# PL.net
KiCad netlist of a schematic drawn in EAGLE
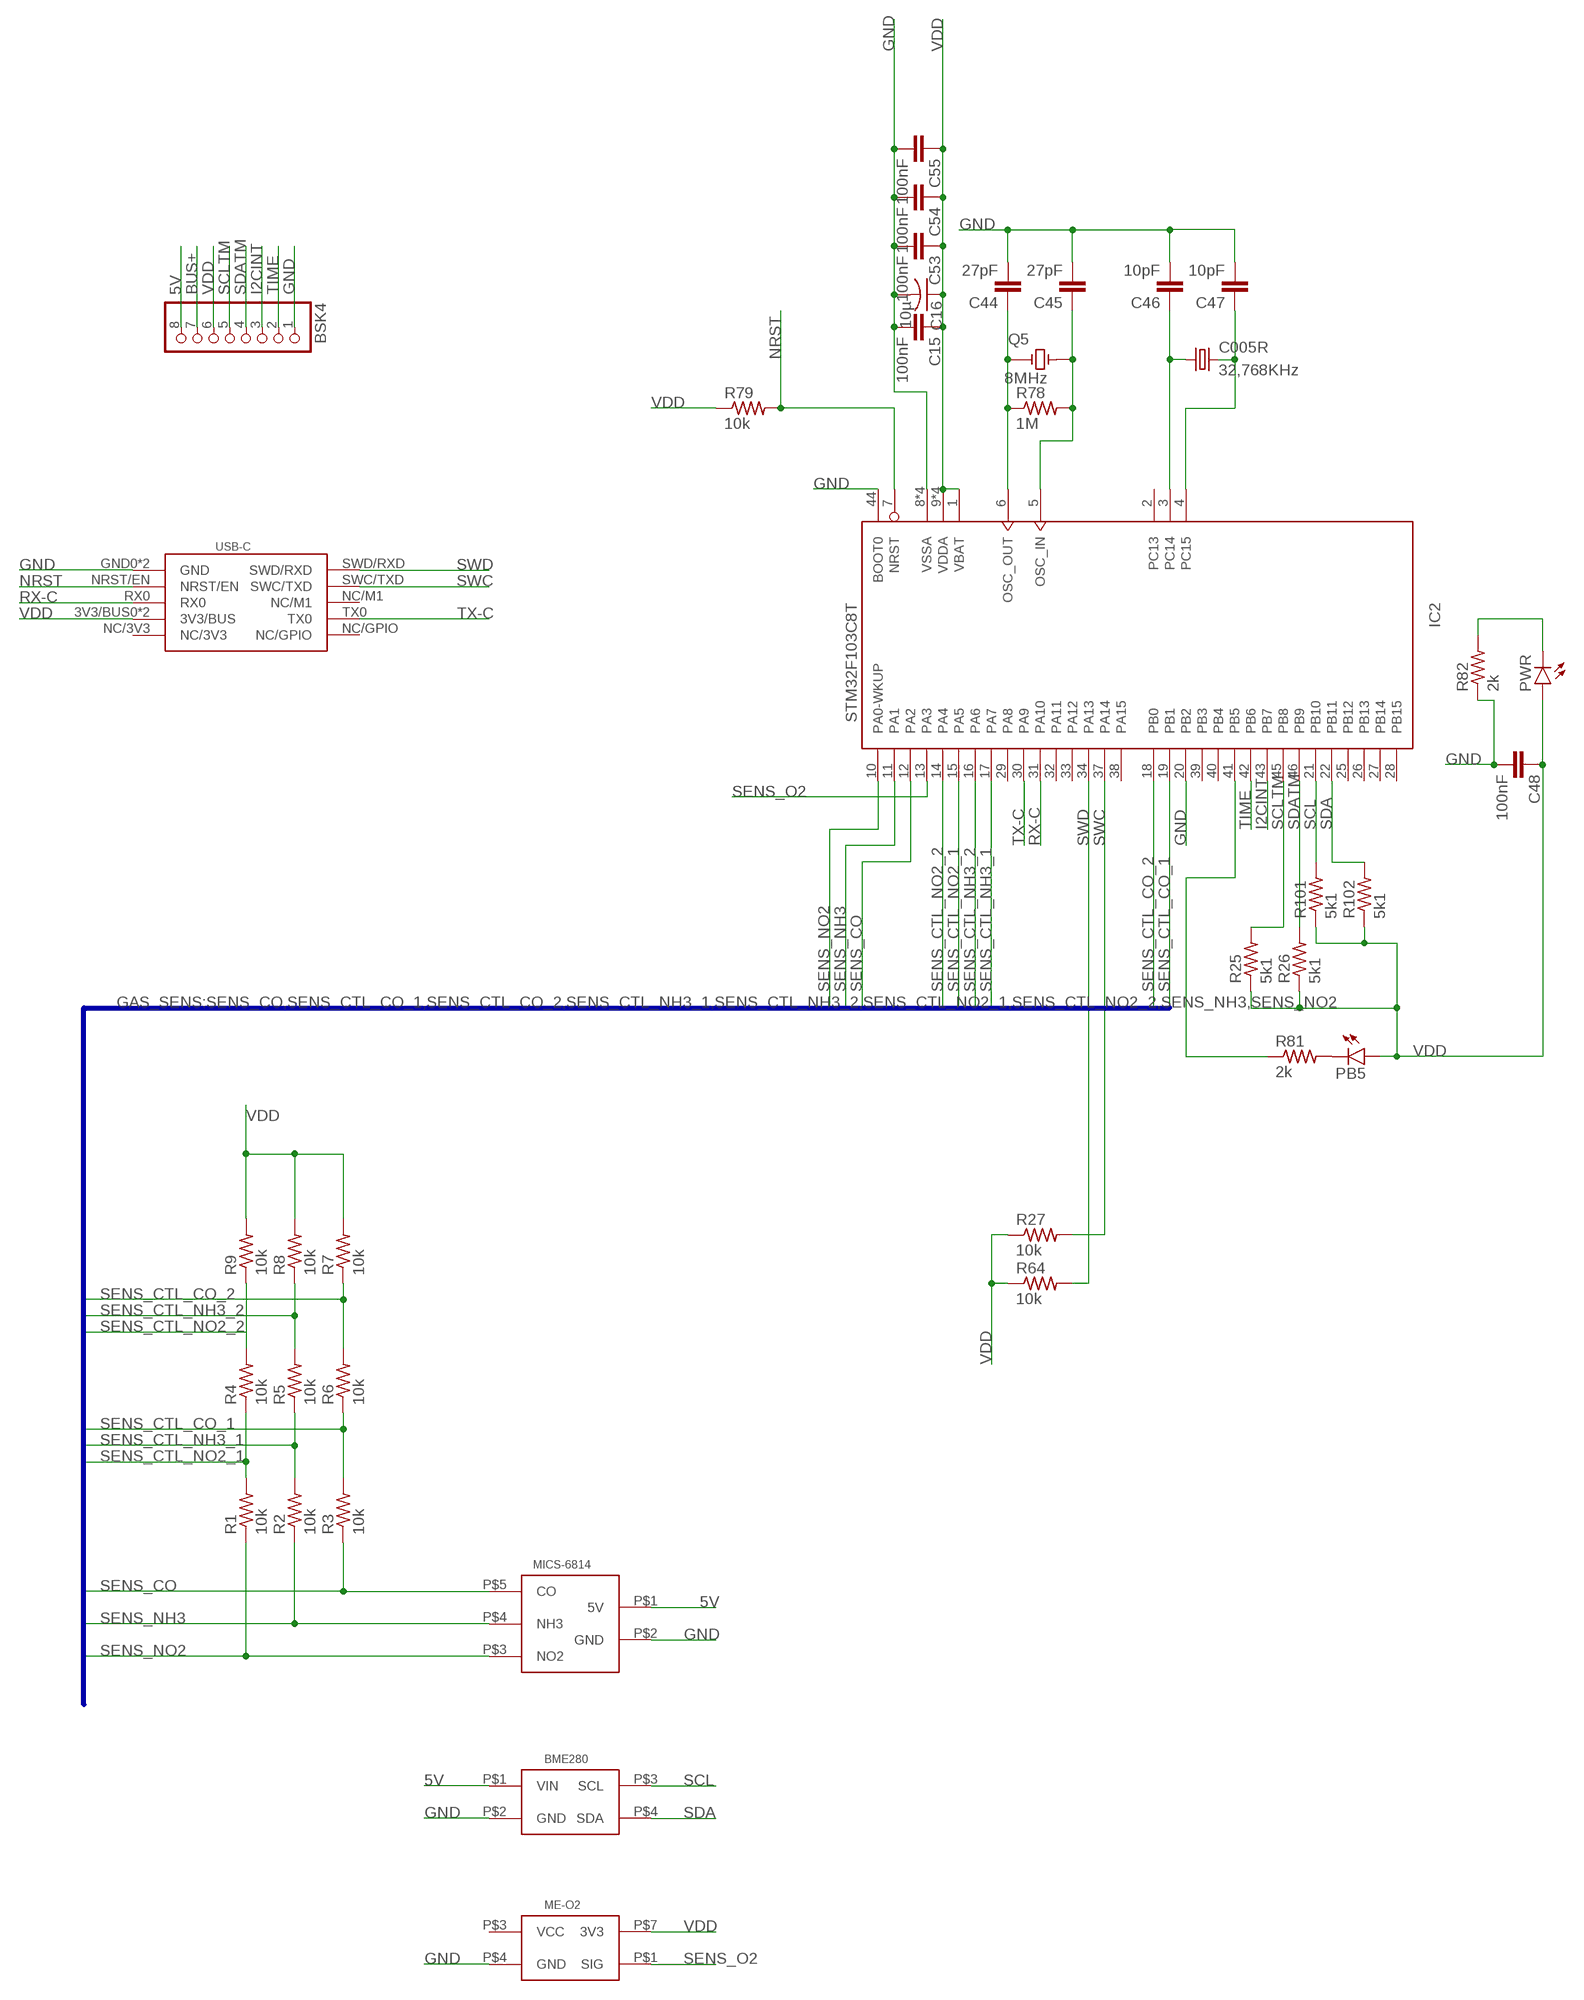
[diagram p0: schematic, sheet 1]

(export (version "E")
  (design (tool "Eeschema 10.0.6"))
  (components
    (comp (ref "BME280")
      (value "BME280")
      (footprint "eagle-import:BME280")
      (libsource (lib "eagle-import") (part "BME280"))
    )
    (comp (ref "BSK4")
      (value "PINHD-1X8")
      (footprint "eagle-import:1X08")
      (libsource (lib "eagle-import") (part "PINHD-1X8"))
    )
    (comp (ref "C005R")
      (value "32,768KHz")
      (footprint "eagle-import:C005R")
      (libsource (lib "eagle-import") (part "C005R"))
    )
    (comp (ref "C15")
      (value "100nF")
      (footprint "eagle-import:C0603")
      (libsource (lib "eagle-import") (part "C-EUC0603"))
    )
    (comp (ref "C16")
      (value "10µ")
      (footprint "eagle-import:C1206")
      (libsource (lib "eagle-import") (part "C-USC1206"))
    )
    (comp (ref "C44")
      (value "27pF")
      (footprint "eagle-import:C0603")
      (libsource (lib "eagle-import") (part "C-EUC0603"))
    )
    (comp (ref "C45")
      (value "27pF")
      (footprint "eagle-import:C0603")
      (libsource (lib "eagle-import") (part "C-EUC0603"))
    )
    (comp (ref "C46")
      (value "10pF")
      (footprint "eagle-import:C0603")
      (libsource (lib "eagle-import") (part "C-EUC0603"))
    )
    (comp (ref "C47")
      (value "10pF")
      (footprint "eagle-import:C0603")
      (libsource (lib "eagle-import") (part "C-EUC0603"))
    )
    (comp (ref "C48")
      (value "100nF")
      (footprint "eagle-import:C0603")
      (libsource (lib "eagle-import") (part "C-EUC0603"))
    )
    (comp (ref "C53")
      (value "100nF")
      (footprint "eagle-import:C0603")
      (libsource (lib "eagle-import") (part "C-EUC0603"))
    )
    (comp (ref "C54")
      (value "100nF")
      (footprint "eagle-import:C0603")
      (libsource (lib "eagle-import") (part "C-EUC0603"))
    )
    (comp (ref "C55")
      (value "100nF")
      (footprint "eagle-import:C0603")
      (libsource (lib "eagle-import") (part "C-EUC0603"))
    )
    (comp (ref "IC2")
      (value "STM32F103C8T")
      (footprint "eagle-import:LQFP48")
      (libsource (lib "eagle-import") (part "STM32F103CT8"))
    )
    (comp (ref "ME-O2")
      (value "ME-O2")
      (footprint "eagle-import:ME-O2")
      (libsource (lib "eagle-import") (part "ME-O2"))
    )
    (comp (ref "MICS-6814")
      (value "MICS-6814")
      (footprint "eagle-import:MICS-6814")
      (libsource (lib "eagle-import") (part "MICS-6814"))
    )
    (comp (ref "PB5")
      (value "LEDCHIPLED_0603")
      (footprint "eagle-import:CHIPLED_0603")
      (libsource (lib "eagle-import") (part "LEDCHIPLED_0603"))
    )
    (comp (ref "PWR")
      (value "LEDCHIPLED_0603")
      (footprint "eagle-import:CHIPLED_0603")
      (libsource (lib "eagle-import") (part "LEDCHIPLED_0603"))
    )
    (comp (ref "Q5")
      (value "8MHz")
      (footprint "eagle-import:XTAL_9C-8.000MEEJ-T")
      (fields (field (name "MF") "TXC CORPORATION") (field (name "MP") "9C-8.000MEEJ-T"))
      (libsource (lib "eagle-import") (part "9C-8.000MEEJ-T"))
    )
    (comp (ref "R1")
      (value "10k")
      (footprint "eagle-import:R0603")
      (libsource (lib "eagle-import") (part "R-US_R0603"))
    )
    (comp (ref "R2")
      (value "10k")
      (footprint "eagle-import:R0603")
      (libsource (lib "eagle-import") (part "R-US_R0603"))
    )
    (comp (ref "R3")
      (value "10k")
      (footprint "eagle-import:R0603")
      (libsource (lib "eagle-import") (part "R-US_R0603"))
    )
    (comp (ref "R4")
      (value "10k")
      (footprint "eagle-import:R0603")
      (libsource (lib "eagle-import") (part "R-US_R0603"))
    )
    (comp (ref "R5")
      (value "10k")
      (footprint "eagle-import:R0603")
      (libsource (lib "eagle-import") (part "R-US_R0603"))
    )
    (comp (ref "R6")
      (value "10k")
      (footprint "eagle-import:R0603")
      (libsource (lib "eagle-import") (part "R-US_R0603"))
    )
    (comp (ref "R7")
      (value "10k")
      (footprint "eagle-import:R0603")
      (libsource (lib "eagle-import") (part "R-US_R0603"))
    )
    (comp (ref "R8")
      (value "10k")
      (footprint "eagle-import:R0603")
      (libsource (lib "eagle-import") (part "R-US_R0603"))
    )
    (comp (ref "R9")
      (value "10k")
      (footprint "eagle-import:R0603")
      (libsource (lib "eagle-import") (part "R-US_R0603"))
    )
    (comp (ref "R25")
      (value "5k1")
      (footprint "eagle-import:R0603")
      (libsource (lib "eagle-import") (part "R-US_R0603"))
    )
    (comp (ref "R26")
      (value "5k1")
      (footprint "eagle-import:R0603")
      (libsource (lib "eagle-import") (part "R-US_R0603"))
    )
    (comp (ref "R27")
      (value "10k")
      (footprint "eagle-import:R0603")
      (libsource (lib "eagle-import") (part "R-US_R0603"))
    )
    (comp (ref "R64")
      (value "10k")
      (footprint "eagle-import:R0603")
      (libsource (lib "eagle-import") (part "R-US_R0603"))
    )
    (comp (ref "R78")
      (value "1M")
      (footprint "eagle-import:R0603")
      (libsource (lib "eagle-import") (part "R-US_R0603"))
    )
    (comp (ref "R79")
      (value "10k")
      (footprint "eagle-import:R0603")
      (libsource (lib "eagle-import") (part "R-US_R0603"))
    )
    (comp (ref "R81")
      (value "2k")
      (footprint "eagle-import:R0603")
      (libsource (lib "eagle-import") (part "R-US_R0603"))
    )
    (comp (ref "R82")
      (value "2k")
      (footprint "eagle-import:R0603")
      (libsource (lib "eagle-import") (part "R-US_R0603"))
    )
    (comp (ref "R101")
      (value "5k1")
      (footprint "eagle-import:R0603")
      (libsource (lib "eagle-import") (part "R-US_R0603"))
    )
    (comp (ref "R102")
      (value "5k1")
      (footprint "eagle-import:R0603")
      (libsource (lib "eagle-import") (part "R-US_R0603"))
    )
    (comp (ref "USB-C")
      (value "USB-C")
      (footprint "eagle-import:USB-C")
      (libsource (lib "eagle-import") (part "USB-C"))
    )
  )
  (nets
    (net (code "2") (name "/5V") (class "Default")
      (node (ref "BME280") (pin "P$1") (pinfunction "VIN_P$1") (pintype "bidirectional"))
      (node (ref "BSK4") (pin "8") (pinfunction "8_8") (pintype "passive"))
      (node (ref "MICS-6814") (pin "P$1") (pinfunction "5V_P$1") (pintype "bidirectional"))
    )
    (net (code "3") (name "/BUS+") (class "Default")
      (node (ref "BSK4") (pin "7") (pinfunction "7_7") (pintype "passive"))
    )
    (net (code "4") (name "/GND") (class "Default")
      (node (ref "BME280") (pin "P$2") (pinfunction "GND_P$2") (pintype "bidirectional"))
      (node (ref "BSK4") (pin "1") (pinfunction "1_1") (pintype "passive"))
      (node (ref "C15") (pin "2") (pinfunction "2_2") (pintype "passive"))
      (node (ref "C16") (pin "2") (pinfunction "2_2") (pintype "passive"))
      (node (ref "C44") (pin "2") (pinfunction "2_2") (pintype "passive"))
      (node (ref "C45") (pin "2") (pinfunction "2_2") (pintype "passive"))
      (node (ref "C46") (pin "2") (pinfunction "2_2") (pintype "passive"))
      (node (ref "C47") (pin "2") (pinfunction "2_2") (pintype "passive"))
      (node (ref "C48") (pin "2") (pinfunction "2_2") (pintype "passive"))
      (node (ref "C53") (pin "2") (pinfunction "2_2") (pintype "passive"))
      (node (ref "C54") (pin "2") (pinfunction "2_2") (pintype "passive"))
      (node (ref "C55") (pin "2") (pinfunction "2_2") (pintype "passive"))
      (node (ref "IC2") (pin "20") (pinfunction "PB2_20") (pintype "bidirectional"))
      (node (ref "IC2") (pin "23") (pinfunction "VSSA_23") (pintype "power_in"))
      (node (ref "IC2") (pin "35") (pinfunction "VSSA_35") (pintype "power_in"))
      (node (ref "IC2") (pin "44") (pinfunction "BOOT0_44") (pintype "input"))
      (node (ref "IC2") (pin "47") (pinfunction "VSSA_47") (pintype "power_in"))
      (node (ref "IC2") (pin "8") (pinfunction "VSSA_8") (pintype "power_in"))
      (node (ref "ME-O2") (pin "P$4") (pinfunction "GND_P$4") (pintype "bidirectional"))
      (node (ref "MICS-6814") (pin "P$2") (pinfunction "GND_P$2") (pintype "bidirectional"))
      (node (ref "R82") (pin "1") (pinfunction "1_1") (pintype "passive"))
      (node (ref "USB-C") (pin "GND0") (pinfunction "GND_GND0") (pintype "bidirectional"))
      (node (ref "USB-C") (pin "GND1") (pinfunction "GND_GND1") (pintype "bidirectional"))
    )
    (net (code "5") (name "/I2CINT") (class "Default")
      (node (ref "BSK4") (pin "3") (pinfunction "3_3") (pintype "passive"))
      (node (ref "IC2") (pin "43") (pinfunction "PB7_43") (pintype "bidirectional"))
    )
    (net (code "6") (name "/NRST") (class "Default")
      (node (ref "IC2") (pin "7") (pinfunction "NRST_7") (pintype "bidirectional"))
      (node (ref "R79") (pin "2") (pinfunction "2_2") (pintype "passive"))
      (node (ref "USB-C") (pin "NRST/EN") (pinfunction "NRST/EN_NRST/EN") (pintype "bidirectional"))
    )
    (net (code "7") (name "/RX-C") (class "Default")
      (node (ref "IC2") (pin "31") (pinfunction "PA10_31") (pintype "bidirectional"))
      (node (ref "USB-C") (pin "RX0") (pinfunction "RX0_RX0") (pintype "bidirectional"))
    )
    (net (code "8") (name "/SCL") (class "Default")
      (node (ref "BME280") (pin "P$3") (pinfunction "SCL_P$3") (pintype "bidirectional"))
      (node (ref "IC2") (pin "21") (pinfunction "PB10_21") (pintype "bidirectional"))
      (node (ref "R101") (pin "2") (pinfunction "2_2") (pintype "passive"))
    )
    (net (code "9") (name "/SCLTM") (class "Default")
      (node (ref "BSK4") (pin "5") (pinfunction "5_5") (pintype "passive"))
      (node (ref "IC2") (pin "45") (pinfunction "PB8_45") (pintype "bidirectional"))
      (node (ref "R25") (pin "2") (pinfunction "2_2") (pintype "passive"))
    )
    (net (code "10") (name "/SDA") (class "Default")
      (node (ref "BME280") (pin "P$4") (pinfunction "SDA_P$4") (pintype "bidirectional"))
      (node (ref "IC2") (pin "22") (pinfunction "PB11_22") (pintype "bidirectional"))
      (node (ref "R102") (pin "2") (pinfunction "2_2") (pintype "passive"))
    )
    (net (code "11") (name "/SDATM") (class "Default")
      (node (ref "BSK4") (pin "4") (pinfunction "4_4") (pintype "passive"))
      (node (ref "IC2") (pin "46") (pinfunction "PB9_46") (pintype "bidirectional"))
      (node (ref "R26") (pin "2") (pinfunction "2_2") (pintype "passive"))
    )
    (net (code "12") (name "/SENS_CO") (class "Default")
      (node (ref "IC2") (pin "12") (pinfunction "PA2_12") (pintype "bidirectional"))
      (node (ref "MICS-6814") (pin "P$5") (pinfunction "CO_P$5") (pintype "bidirectional"))
      (node (ref "R3") (pin "1") (pinfunction "1_1") (pintype "passive"))
    )
    (net (code "13") (name "/SENS_CTL_CO_1") (class "Default")
      (node (ref "IC2") (pin "19") (pinfunction "PB1_19") (pintype "bidirectional"))
      (node (ref "R3") (pin "2") (pinfunction "2_2") (pintype "passive"))
      (node (ref "R6") (pin "1") (pinfunction "1_1") (pintype "passive"))
    )
    (net (code "14") (name "/SENS_CTL_CO_2") (class "Default")
      (node (ref "IC2") (pin "18") (pinfunction "PB0_18") (pintype "bidirectional"))
      (node (ref "R6") (pin "2") (pinfunction "2_2") (pintype "passive"))
      (node (ref "R7") (pin "1") (pinfunction "1_1") (pintype "passive"))
    )
    (net (code "15") (name "/SENS_CTL_NH3_1") (class "Default")
      (node (ref "IC2") (pin "17") (pinfunction "PA7_17") (pintype "bidirectional"))
      (node (ref "R2") (pin "2") (pinfunction "2_2") (pintype "passive"))
      (node (ref "R5") (pin "1") (pinfunction "1_1") (pintype "passive"))
    )
    (net (code "16") (name "/SENS_CTL_NH3_2") (class "Default")
      (node (ref "IC2") (pin "16") (pinfunction "PA6_16") (pintype "bidirectional"))
      (node (ref "R5") (pin "2") (pinfunction "2_2") (pintype "passive"))
      (node (ref "R8") (pin "1") (pinfunction "1_1") (pintype "passive"))
    )
    (net (code "17") (name "/SENS_CTL_NO2_1") (class "Default")
      (node (ref "IC2") (pin "15") (pinfunction "PA5_15") (pintype "bidirectional"))
      (node (ref "R1") (pin "2") (pinfunction "2_2") (pintype "passive"))
      (node (ref "R4") (pin "1") (pinfunction "1_1") (pintype "passive"))
    )
    (net (code "18") (name "/SENS_CTL_NO2_2") (class "Default")
      (node (ref "IC2") (pin "14") (pinfunction "PA4_14") (pintype "bidirectional"))
      (node (ref "R4") (pin "2") (pinfunction "2_2") (pintype "passive"))
      (node (ref "R9") (pin "1") (pinfunction "1_1") (pintype "passive"))
    )
    (net (code "19") (name "/SENS_NH3") (class "Default")
      (node (ref "IC2") (pin "11") (pinfunction "PA1_11") (pintype "bidirectional"))
      (node (ref "MICS-6814") (pin "P$4") (pinfunction "NH3_P$4") (pintype "bidirectional"))
      (node (ref "R2") (pin "1") (pinfunction "1_1") (pintype "passive"))
    )
    (net (code "20") (name "/SENS_NO2") (class "Default")
      (node (ref "IC2") (pin "10") (pinfunction "PA0-WKUP_10") (pintype "bidirectional"))
      (node (ref "MICS-6814") (pin "P$3") (pinfunction "NO2_P$3") (pintype "bidirectional"))
      (node (ref "R1") (pin "1") (pinfunction "1_1") (pintype "passive"))
    )
    (net (code "21") (name "/SENS_O2") (class "Default")
      (node (ref "IC2") (pin "13") (pinfunction "PA3_13") (pintype "bidirectional"))
      (node (ref "ME-O2") (pin "P$1") (pinfunction "SIG_P$1") (pintype "bidirectional"))
    )
    (net (code "22") (name "/SWC") (class "Default")
      (node (ref "IC2") (pin "37") (pinfunction "PA14_37") (pintype "bidirectional"))
      (node (ref "R27") (pin "2") (pinfunction "2_2") (pintype "passive"))
      (node (ref "USB-C") (pin "SWC/TXD") (pinfunction "SWC/TXD_SWC/TXD") (pintype "bidirectional"))
    )
    (net (code "23") (name "/SWD") (class "Default")
      (node (ref "IC2") (pin "34") (pinfunction "PA13_34") (pintype "bidirectional"))
      (node (ref "R64") (pin "2") (pinfunction "2_2") (pintype "passive"))
      (node (ref "USB-C") (pin "SWD/RXD") (pinfunction "SWD/RXD_SWD/RXD") (pintype "bidirectional"))
    )
    (net (code "24") (name "/TIME") (class "Default")
      (node (ref "BSK4") (pin "2") (pinfunction "2_2") (pintype "passive"))
      (node (ref "IC2") (pin "42") (pinfunction "PB6_42") (pintype "bidirectional"))
    )
    (net (code "25") (name "/TX-C") (class "Default")
      (node (ref "IC2") (pin "30") (pinfunction "PA9_30") (pintype "bidirectional"))
      (node (ref "USB-C") (pin "TX0") (pinfunction "TX0_TX0") (pintype "bidirectional"))
    )
    (net (code "26") (name "/VDD") (class "Default")
      (node (ref "BSK4") (pin "6") (pinfunction "6_6") (pintype "passive"))
      (node (ref "C15") (pin "1") (pinfunction "1_1") (pintype "passive"))
      (node (ref "C16") (pin "1") (pinfunction "1_1") (pintype "passive"))
      (node (ref "C48") (pin "1") (pinfunction "1_1") (pintype "passive"))
      (node (ref "C53") (pin "1") (pinfunction "1_1") (pintype "passive"))
      (node (ref "C54") (pin "1") (pinfunction "1_1") (pintype "passive"))
      (node (ref "C55") (pin "1") (pinfunction "1_1") (pintype "passive"))
      (node (ref "IC2") (pin "1") (pinfunction "VBAT_1") (pintype "power_in"))
      (node (ref "IC2") (pin "24") (pinfunction "VDDA_24") (pintype "power_in"))
      (node (ref "IC2") (pin "36") (pinfunction "VDDA_36") (pintype "power_in"))
      (node (ref "IC2") (pin "48") (pinfunction "VDDA_48") (pintype "power_in"))
      (node (ref "IC2") (pin "9") (pinfunction "VDDA_9") (pintype "power_in"))
      (node (ref "ME-O2") (pin "P$7") (pinfunction "3V3_P$7") (pintype "bidirectional"))
      (node (ref "PB5") (pin "A") (pinfunction "A_A") (pintype "passive"))
      (node (ref "PWR") (pin "A") (pinfunction "A_A") (pintype "passive"))
      (node (ref "R101") (pin "1") (pinfunction "1_1") (pintype "passive"))
      (node (ref "R102") (pin "1") (pinfunction "1_1") (pintype "passive"))
      (node (ref "R25") (pin "1") (pinfunction "1_1") (pintype "passive"))
      (node (ref "R26") (pin "1") (pinfunction "1_1") (pintype "passive"))
      (node (ref "R27") (pin "1") (pinfunction "1_1") (pintype "passive"))
      (node (ref "R64") (pin "1") (pinfunction "1_1") (pintype "passive"))
      (node (ref "R7") (pin "2") (pinfunction "2_2") (pintype "passive"))
      (node (ref "R79") (pin "1") (pinfunction "1_1") (pintype "passive"))
      (node (ref "R8") (pin "2") (pinfunction "2_2") (pintype "passive"))
      (node (ref "R9") (pin "2") (pinfunction "2_2") (pintype "passive"))
      (node (ref "USB-C") (pin "3V3/BUS0") (pinfunction "3V3/BUS_3V3/BUS0") (pintype "bidirectional"))
      (node (ref "USB-C") (pin "3V3/BUS1") (pinfunction "3V3/BUS_3V3/BUS1") (pintype "bidirectional"))
    )
    (net (code "28") (name "Net-(C005R-1)") (class "Default")
      (node (ref "C005R") (pin "P$1") (pinfunction "1_P$1") (pintype "passive"))
      (node (ref "C46") (pin "1") (pinfunction "1_1") (pintype "passive"))
      (node (ref "IC2") (pin "3") (pinfunction "PC14_3") (pintype "bidirectional"))
    )
    (net (code "29") (name "Net-(C005R-2)") (class "Default")
      (node (ref "C005R") (pin "P$2") (pinfunction "2_P$2") (pintype "passive"))
      (node (ref "C47") (pin "1") (pinfunction "1_1") (pintype "passive"))
      (node (ref "IC2") (pin "4") (pinfunction "PC15_4") (pintype "bidirectional"))
    )
    (net (code "30") (name "Net-(IC2-OSC_IN)") (class "Default")
      (node (ref "C45") (pin "1") (pinfunction "1_1") (pintype "passive"))
      (node (ref "IC2") (pin "5") (pinfunction "OSC_IN_5") (pintype "bidirectional"))
      (node (ref "Q5") (pin "2") (pinfunction "2_2") (pintype "passive"))
      (node (ref "R78") (pin "2") (pinfunction "2_2") (pintype "passive"))
    )
    (net (code "31") (name "Net-(IC2-OSC_OUT)") (class "Default")
      (node (ref "C44") (pin "1") (pinfunction "1_1") (pintype "passive"))
      (node (ref "IC2") (pin "6") (pinfunction "OSC_OUT_6") (pintype "bidirectional"))
      (node (ref "Q5") (pin "1") (pinfunction "1_1") (pintype "passive"))
      (node (ref "R78") (pin "1") (pinfunction "1_1") (pintype "passive"))
    )
    (net (code "32") (name "Net-(IC2-PB5)") (class "Default")
      (node (ref "IC2") (pin "41") (pinfunction "PB5_41") (pintype "bidirectional"))
      (node (ref "R81") (pin "1") (pinfunction "1_1") (pintype "passive"))
    )
    (net (code "33") (name "Net-(PB5-PadC)") (class "Default")
      (node (ref "PB5") (pin "C") (pinfunction "C_C") (pintype "passive"))
      (node (ref "R81") (pin "2") (pinfunction "2_2") (pintype "passive"))
    )
    (net (code "34") (name "Net-(PWR-PadC)") (class "Default")
      (node (ref "PWR") (pin "C") (pinfunction "C_C") (pintype "passive"))
      (node (ref "R82") (pin "2") (pinfunction "2_2") (pintype "passive"))
    )
    (net (code "35") (name "unconnected-(IC2-PA8-Pad29)") (class "Default")
      (node (ref "IC2") (pin "29") (pinfunction "PA8_29") (pintype "bidirectional"))
    )
    (net (code "36") (name "unconnected-(IC2-PA11-Pad32)") (class "Default")
      (node (ref "IC2") (pin "32") (pinfunction "PA11_32") (pintype "bidirectional"))
    )
    (net (code "37") (name "unconnected-(IC2-PA12-Pad33)") (class "Default")
      (node (ref "IC2") (pin "33") (pinfunction "PA12_33") (pintype "bidirectional"))
    )
    (net (code "38") (name "unconnected-(IC2-PA15-Pad38)") (class "Default")
      (node (ref "IC2") (pin "38") (pinfunction "PA15_38") (pintype "bidirectional"))
    )
    (net (code "39") (name "unconnected-(IC2-PB3-Pad39)") (class "Default")
      (node (ref "IC2") (pin "39") (pinfunction "PB3_39") (pintype "bidirectional"))
    )
    (net (code "40") (name "unconnected-(IC2-PB4-Pad40)") (class "Default")
      (node (ref "IC2") (pin "40") (pinfunction "PB4_40") (pintype "bidirectional"))
    )
    (net (code "41") (name "unconnected-(IC2-PB12-Pad25)") (class "Default")
      (node (ref "IC2") (pin "25") (pinfunction "PB12_25") (pintype "bidirectional"))
    )
    (net (code "42") (name "unconnected-(IC2-PB13-Pad26)") (class "Default")
      (node (ref "IC2") (pin "26") (pinfunction "PB13_26") (pintype "bidirectional"))
    )
    (net (code "43") (name "unconnected-(IC2-PB14-Pad27)") (class "Default")
      (node (ref "IC2") (pin "27") (pinfunction "PB14_27") (pintype "bidirectional"))
    )
    (net (code "44") (name "unconnected-(IC2-PB15-Pad28)") (class "Default")
      (node (ref "IC2") (pin "28") (pinfunction "PB15_28") (pintype "bidirectional"))
    )
    (net (code "45") (name "unconnected-(IC2-PC13-Pad2)") (class "Default")
      (node (ref "IC2") (pin "2") (pinfunction "PC13_2") (pintype "bidirectional"))
    )
    (net (code "46") (name "unconnected-(ME-O2-VCC-PadP$3)") (class "Default")
      (node (ref "ME-O2") (pin "P$3") (pinfunction "VCC_P$3") (pintype "bidirectional"))
    )
    (net (code "47") (name "unconnected-(USB-C-PadNC{slash}3V3)") (class "Default")
      (node (ref "USB-C") (pin "NC/3V3") (pinfunction "NC/3V3_NC/3V3") (pintype "bidirectional"))
    )
    (net (code "48") (name "unconnected-(USB-C-PadNC{slash}GPIO)") (class "Default")
      (node (ref "USB-C") (pin "NC/GPIO") (pinfunction "NC/GPIO_NC/GPIO") (pintype "bidirectional"))
    )
    (net (code "49") (name "unconnected-(USB-C-PadNC{slash}M1)") (class "Default")
      (node (ref "USB-C") (pin "NC/M1") (pinfunction "NC/M1_NC/M1") (pintype "bidirectional"))
    )
  )
)
